# Arduino_Mopho_Connectors.net
KiCad netlist of a schematic drawn in Altium Designer
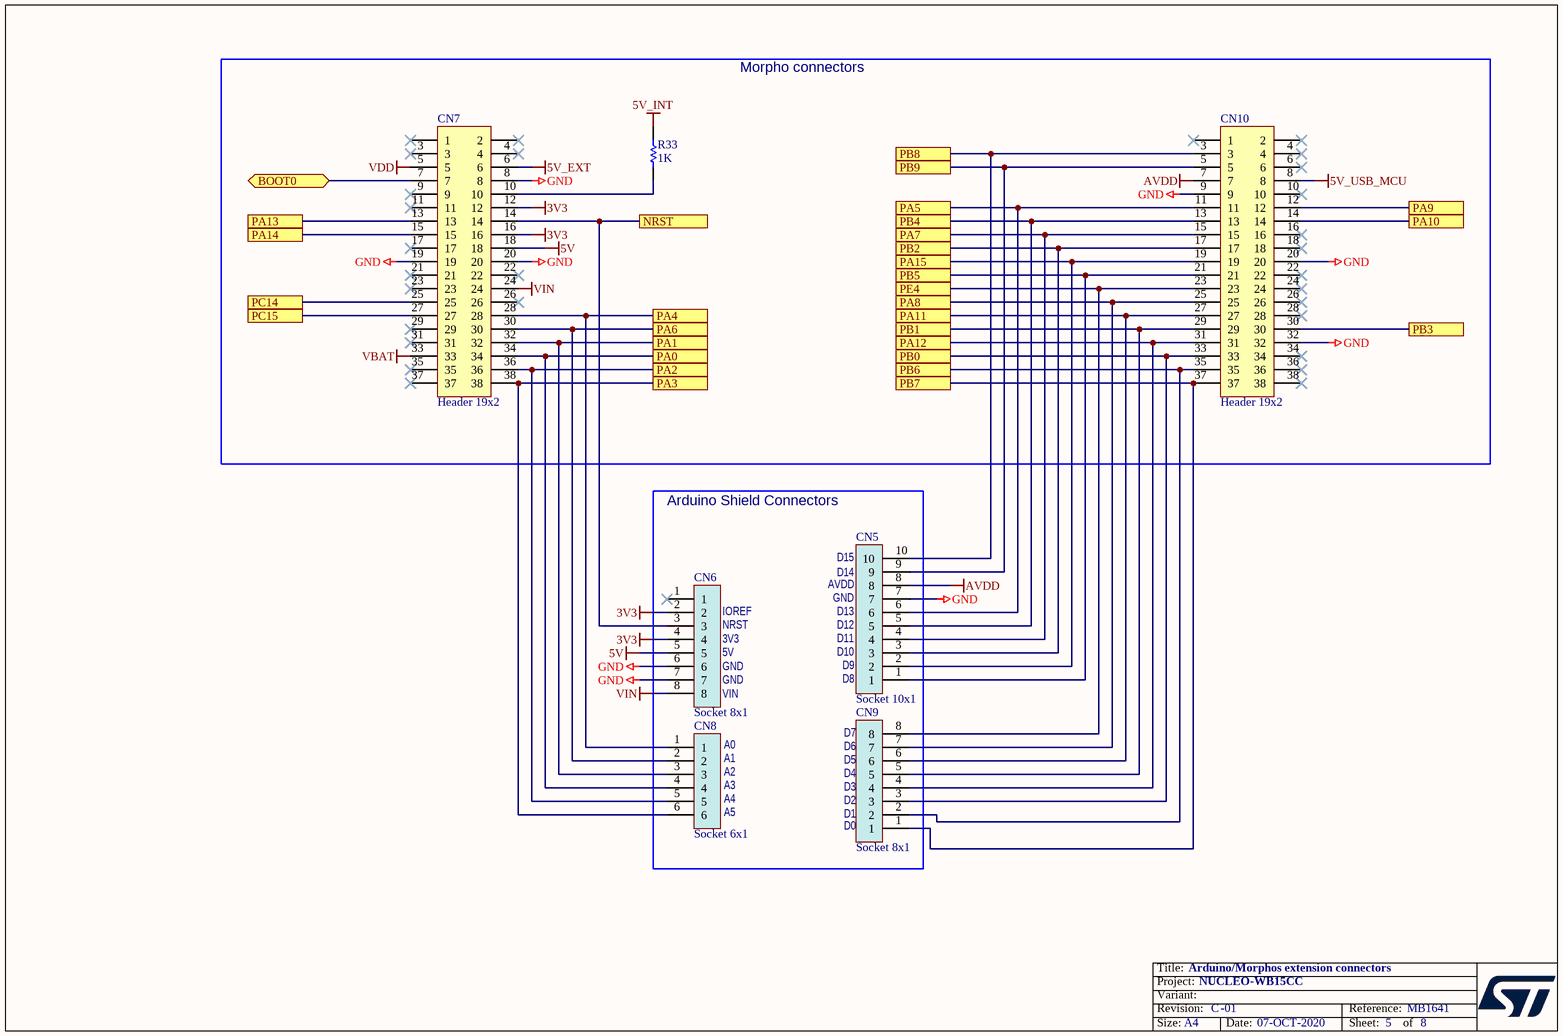
[diagram p0: Arduino_Mopho_Connectors.SchDoc]

(export (version "E")
  (design (tool "Eeschema 10.0.6"))
  (components
    (comp (ref "CN5")
      (value "Socket 10x1")
      (footprint "CON_SAMTEC_SSW-110-01-X-S")
      (description "Socket 10x1, 2.54mm, VR, TH, height 8.51/2.64mm")
      (fields
        (field (name "INTERNAL_PART_NUMBER") "MCD-02080")
        (field (name "MANUFACTURER_PART_NUMBER") "SSW-110-01-G-S")
      )
      (libsource (lib "MCD_PARTS_database") (part "Socket 10x1"))
    )
    (comp (ref "CN6")
      (value "Socket 8x1")
      (footprint "CON_SAMTEC_SSW-108-01-X-S")
      (description "Socket 8x1, 2.54mm, VR, TH, height 8.51/2.64mm")
      (fields
        (field (name "INTERNAL_PART_NUMBER") "MCD-01743")
        (field (name "MANUFACTURER_PART_NUMBER") "SSW-108-01-G-S")
      )
      (libsource (lib "MCD_PARTS_database") (part "Socket 8x1"))
    )
    (comp (ref "CN7")
      (value "Header 19x2")
      (footprint "CON_SAMTEC_TSW-119-09-X-D")
      (description "Header, 19x2, 2,54mm, VR, TH, Height 5.84mm/10.16mm")
      (fields
        (field (name "INTERNAL_PART_NUMBER") "MCD-00213")
        (field (name "MANUFACTURER_PART_NUMBER") "TSW-119-09-G-D")
      )
      (libsource (lib "MCD_PARTS_database") (part "Header 19x2"))
    )
    (comp (ref "CN8")
      (value "Socket 6x1")
      (footprint "CON_SAMTEC_SSW-106-01-X-S")
      (description "Socket 6x1, 2.54mm, VR, TH, height 8.51/2.64mm")
      (fields
        (field (name "INTERNAL_PART_NUMBER") "MCD-02079")
        (field (name "MANUFACTURER_PART_NUMBER") "SSW-106-01-G-S")
      )
      (libsource (lib "MCD_PARTS_database") (part "Socket 6x1"))
    )
    (comp (ref "CN9")
      (value "Socket 8x1")
      (footprint "CON_SAMTEC_SSW-108-01-X-S")
      (description "Socket 8x1, 2.54mm, VR, TH, height 8.51/2.64mm")
      (fields
        (field (name "INTERNAL_PART_NUMBER") "MCD-01743")
        (field (name "MANUFACTURER_PART_NUMBER") "SSW-108-01-G-S")
      )
      (libsource (lib "") (part "Socket 8x1_1"))
    )
    (comp (ref "CN10")
      (value "Header 19x2")
      (footprint "CON_SAMTEC_TSW-119-09-X-D")
      (description "Header, 19x2, 2,54mm, VR, TH, Height 5.84mm/10.16mm")
      (fields
        (field (name "INTERNAL_PART_NUMBER") "MCD-00213")
        (field (name "MANUFACTURER_PART_NUMBER") "TSW-119-09-G-D")
      )
      (libsource (lib "MCD_PARTS_database") (part "Header 19x2"))
    )
    (comp (ref "R33")
      (value "1K")
      (footprint "R0402")
      (description "Resistor,1K,0402,1%,1/16W")
      (fields
        (field (name "INTERNAL_PART_NUMBER") "MCD-00061")
        (field (name "MANUFACTURER_PART_NUMBER") "RC0402FR-071KL")
      )
      (libsource (lib "MCD_PARTS_database") (part "Resistor"))
    )
  )
  (nets
    (net (code "1") (name "/BOOT0") (class "Default")
      (node (ref "CN7") (pin "7") (pinfunction "7_7") (pintype "passive"))
    )
    (net (code "2") (name "/NRST") (class "Default")
      (node (ref "CN6") (pin "3") (pinfunction "3_3") (pintype "passive"))
      (node (ref "CN7") (pin "14") (pinfunction "14_14") (pintype "passive"))
    )
    (net (code "3") (name "/PA0") (class "Default")
      (node (ref "CN7") (pin "34") (pinfunction "34_34") (pintype "passive"))
      (node (ref "CN8") (pin "4") (pinfunction "4_4") (pintype "passive"))
    )
    (net (code "4") (name "/PA1") (class "Default")
      (node (ref "CN7") (pin "32") (pinfunction "32_32") (pintype "passive"))
      (node (ref "CN8") (pin "3") (pinfunction "3_3") (pintype "passive"))
    )
    (net (code "5") (name "/PA2") (class "Default")
      (node (ref "CN7") (pin "36") (pinfunction "36_36") (pintype "passive"))
      (node (ref "CN8") (pin "5") (pinfunction "5_5") (pintype "passive"))
    )
    (net (code "6") (name "/PA3") (class "Default")
      (node (ref "CN7") (pin "38") (pinfunction "38_38") (pintype "passive"))
      (node (ref "CN8") (pin "6") (pinfunction "6_6") (pintype "passive"))
    )
    (net (code "7") (name "/PA4") (class "Default")
      (node (ref "CN7") (pin "28") (pinfunction "28_28") (pintype "passive"))
      (node (ref "CN8") (pin "1") (pinfunction "1_1") (pintype "passive"))
    )
    (net (code "8") (name "/PA5") (class "Default")
      (node (ref "CN10") (pin "11") (pinfunction "11_11") (pintype "passive"))
      (node (ref "CN5") (pin "6") (pinfunction "6_6") (pintype "passive"))
    )
    (net (code "9") (name "/PA6") (class "Default")
      (node (ref "CN7") (pin "30") (pinfunction "30_30") (pintype "passive"))
      (node (ref "CN8") (pin "2") (pinfunction "2_2") (pintype "passive"))
    )
    (net (code "10") (name "/PA7") (class "Default")
      (node (ref "CN10") (pin "15") (pinfunction "15_15") (pintype "passive"))
      (node (ref "CN5") (pin "4") (pinfunction "4_4") (pintype "passive"))
    )
    (net (code "11") (name "/PA8") (class "Default")
      (node (ref "CN10") (pin "25") (pinfunction "25_25") (pintype "passive"))
      (node (ref "CN9") (pin "7") (pinfunction "7_7") (pintype "passive"))
    )
    (net (code "12") (name "/PA9") (class "Default")
      (node (ref "CN10") (pin "12") (pinfunction "12_12") (pintype "passive"))
    )
    (net (code "13") (name "/PA10") (class "Default")
      (node (ref "CN10") (pin "14") (pinfunction "14_14") (pintype "passive"))
    )
    (net (code "14") (name "/PA11") (class "Default")
      (node (ref "CN10") (pin "27") (pinfunction "27_27") (pintype "passive"))
      (node (ref "CN9") (pin "6") (pinfunction "6_6") (pintype "passive"))
    )
    (net (code "15") (name "/PA12") (class "Default")
      (node (ref "CN10") (pin "31") (pinfunction "31_31") (pintype "passive"))
      (node (ref "CN9") (pin "4") (pinfunction "4_4") (pintype "passive"))
    )
    (net (code "16") (name "/PA13") (class "Default")
      (node (ref "CN7") (pin "13") (pinfunction "13_13") (pintype "passive"))
    )
    (net (code "17") (name "/PA14") (class "Default")
      (node (ref "CN7") (pin "15") (pinfunction "15_15") (pintype "passive"))
    )
    (net (code "18") (name "/PA15") (class "Default")
      (node (ref "CN10") (pin "19") (pinfunction "19_19") (pintype "passive"))
      (node (ref "CN5") (pin "2") (pinfunction "2_2") (pintype "passive"))
    )
    (net (code "19") (name "/PB0") (class "Default")
      (node (ref "CN10") (pin "33") (pinfunction "33_33") (pintype "passive"))
      (node (ref "CN9") (pin "3") (pinfunction "3_3") (pintype "passive"))
    )
    (net (code "20") (name "/PB1") (class "Default")
      (node (ref "CN10") (pin "29") (pinfunction "29_29") (pintype "passive"))
      (node (ref "CN9") (pin "5") (pinfunction "5_5") (pintype "passive"))
    )
    (net (code "21") (name "/PB2") (class "Default")
      (node (ref "CN10") (pin "17") (pinfunction "17_17") (pintype "passive"))
      (node (ref "CN5") (pin "3") (pinfunction "3_3") (pintype "passive"))
    )
    (net (code "22") (name "/PB3") (class "Default")
      (node (ref "CN10") (pin "30") (pinfunction "30_30") (pintype "passive"))
    )
    (net (code "23") (name "/PB4") (class "Default")
      (node (ref "CN10") (pin "13") (pinfunction "13_13") (pintype "passive"))
      (node (ref "CN5") (pin "5") (pinfunction "5_5") (pintype "passive"))
    )
    (net (code "24") (name "/PB5") (class "Default")
      (node (ref "CN10") (pin "21") (pinfunction "21_21") (pintype "passive"))
      (node (ref "CN5") (pin "1") (pinfunction "1_1") (pintype "passive"))
    )
    (net (code "25") (name "/PB6") (class "Default")
      (node (ref "CN10") (pin "35") (pinfunction "35_35") (pintype "passive"))
      (node (ref "CN9") (pin "2") (pinfunction "2_2") (pintype "passive"))
    )
    (net (code "26") (name "/PB7") (class "Default")
      (node (ref "CN10") (pin "37") (pinfunction "37_37") (pintype "passive"))
      (node (ref "CN9") (pin "1") (pinfunction "1_1") (pintype "passive"))
    )
    (net (code "27") (name "/PB8") (class "Default")
      (node (ref "CN10") (pin "3") (pinfunction "3_3") (pintype "passive"))
      (node (ref "CN5") (pin "10") (pinfunction "10_10") (pintype "passive"))
    )
    (net (code "28") (name "/PB9") (class "Default")
      (node (ref "CN10") (pin "5") (pinfunction "5_5") (pintype "passive"))
      (node (ref "CN5") (pin "9") (pinfunction "9_9") (pintype "passive"))
    )
    (net (code "29") (name "/PC14") (class "Default")
      (node (ref "CN7") (pin "25") (pinfunction "25_25") (pintype "passive"))
    )
    (net (code "30") (name "/PC15") (class "Default")
      (node (ref "CN7") (pin "27") (pinfunction "27_27") (pintype "passive"))
    )
    (net (code "31") (name "/PE4") (class "Default")
      (node (ref "CN10") (pin "23") (pinfunction "23_23") (pintype "passive"))
      (node (ref "CN9") (pin "8") (pinfunction "8_8") (pintype "passive"))
    )
    (net (code "32") (name "3V3") (class "Default")
      (node (ref "CN6") (pin "2") (pinfunction "2_2") (pintype "passive"))
      (node (ref "CN6") (pin "4") (pinfunction "4_4") (pintype "passive"))
      (node (ref "CN7") (pin "12") (pinfunction "12_12") (pintype "passive"))
      (node (ref "CN7") (pin "16") (pinfunction "16_16") (pintype "passive"))
    )
    (net (code "33") (name "5V") (class "Default")
      (node (ref "CN6") (pin "5") (pinfunction "5_5") (pintype "passive"))
      (node (ref "CN7") (pin "18") (pinfunction "18_18") (pintype "passive"))
    )
    (net (code "34") (name "5V_EXT") (class "Default")
      (node (ref "CN7") (pin "6") (pinfunction "6_6") (pintype "passive"))
    )
    (net (code "35") (name "5V_INT") (class "Default")
      (node (ref "R33") (pin "2") (pinfunction "2_2") (pintype "passive"))
    )
    (net (code "36") (name "5V_USB_MCU") (class "Default")
      (node (ref "CN10") (pin "8") (pinfunction "8_8") (pintype "passive"))
    )
    (net (code "37") (name "AVDD") (class "Default")
      (node (ref "CN10") (pin "7") (pinfunction "7_7") (pintype "passive"))
      (node (ref "CN5") (pin "8") (pinfunction "8_8") (pintype "passive"))
    )
    (net (code "38") (name "GND") (class "Default")
      (node (ref "CN10") (pin "20") (pinfunction "20_20") (pintype "passive"))
      (node (ref "CN10") (pin "32") (pinfunction "32_32") (pintype "passive"))
      (node (ref "CN10") (pin "9") (pinfunction "9_9") (pintype "passive"))
      (node (ref "CN5") (pin "7") (pinfunction "7_7") (pintype "passive"))
      (node (ref "CN6") (pin "6") (pinfunction "6_6") (pintype "passive"))
      (node (ref "CN6") (pin "7") (pinfunction "7_7") (pintype "passive"))
      (node (ref "CN7") (pin "19") (pinfunction "19_19") (pintype "passive"))
      (node (ref "CN7") (pin "20") (pinfunction "20_20") (pintype "passive"))
      (node (ref "CN7") (pin "8") (pinfunction "8_8") (pintype "passive"))
    )
    (net (code "39") (name "Net-(CN7-Pad10)") (class "Default")
      (node (ref "CN7") (pin "10") (pinfunction "10_10") (pintype "passive"))
      (node (ref "R33") (pin "1") (pinfunction "1_1") (pintype "passive"))
    )
    (net (code "40") (name "VBAT") (class "Default")
      (node (ref "CN7") (pin "33") (pinfunction "33_33") (pintype "passive"))
    )
    (net (code "41") (name "VDD") (class "Default")
      (node (ref "CN7") (pin "5") (pinfunction "5_5") (pintype "passive"))
    )
    (net (code "42") (name "VIN") (class "Default")
      (node (ref "CN6") (pin "8") (pinfunction "8_8") (pintype "passive"))
      (node (ref "CN7") (pin "24") (pinfunction "24_24") (pintype "passive"))
    )
    (net (code "43") (name "unconnected-(CN6-Pad1)") (class "Default")
      (node (ref "CN6") (pin "1") (pinfunction "1_1") (pintype "passive+no_connect"))
    )
    (net (code "44") (name "unconnected-(CN7-Pad1)") (class "Default")
      (node (ref "CN7") (pin "1") (pinfunction "1_1") (pintype "passive+no_connect"))
    )
    (net (code "45") (name "unconnected-(CN7-Pad2)") (class "Default")
      (node (ref "CN7") (pin "2") (pinfunction "2_2") (pintype "passive+no_connect"))
    )
    (net (code "46") (name "unconnected-(CN7-Pad3)") (class "Default")
      (node (ref "CN7") (pin "3") (pinfunction "3_3") (pintype "passive+no_connect"))
    )
    (net (code "47") (name "unconnected-(CN7-Pad4)") (class "Default")
      (node (ref "CN7") (pin "4") (pinfunction "4_4") (pintype "passive+no_connect"))
    )
    (net (code "48") (name "unconnected-(CN7-Pad9)") (class "Default")
      (node (ref "CN7") (pin "9") (pinfunction "9_9") (pintype "passive+no_connect"))
    )
    (net (code "49") (name "unconnected-(CN7-Pad11)") (class "Default")
      (node (ref "CN7") (pin "11") (pinfunction "11_11") (pintype "passive+no_connect"))
    )
    (net (code "50") (name "unconnected-(CN7-Pad17)") (class "Default")
      (node (ref "CN7") (pin "17") (pinfunction "17_17") (pintype "passive+no_connect"))
    )
    (net (code "51") (name "unconnected-(CN7-Pad21)") (class "Default")
      (node (ref "CN7") (pin "21") (pinfunction "21_21") (pintype "passive+no_connect"))
    )
    (net (code "52") (name "unconnected-(CN7-Pad22)") (class "Default")
      (node (ref "CN7") (pin "22") (pinfunction "22_22") (pintype "passive+no_connect"))
    )
    (net (code "53") (name "unconnected-(CN7-Pad23)") (class "Default")
      (node (ref "CN7") (pin "23") (pinfunction "23_23") (pintype "passive+no_connect"))
    )
    (net (code "54") (name "unconnected-(CN7-Pad26)") (class "Default")
      (node (ref "CN7") (pin "26") (pinfunction "26_26") (pintype "passive+no_connect"))
    )
    (net (code "55") (name "unconnected-(CN7-Pad29)") (class "Default")
      (node (ref "CN7") (pin "29") (pinfunction "29_29") (pintype "passive+no_connect"))
    )
    (net (code "56") (name "unconnected-(CN7-Pad31)") (class "Default")
      (node (ref "CN7") (pin "31") (pinfunction "31_31") (pintype "passive+no_connect"))
    )
    (net (code "57") (name "unconnected-(CN7-Pad35)") (class "Default")
      (node (ref "CN7") (pin "35") (pinfunction "35_35") (pintype "passive+no_connect"))
    )
    (net (code "58") (name "unconnected-(CN7-Pad37)") (class "Default")
      (node (ref "CN7") (pin "37") (pinfunction "37_37") (pintype "passive+no_connect"))
    )
    (net (code "59") (name "unconnected-(CN10-Pad1)") (class "Default")
      (node (ref "CN10") (pin "1") (pinfunction "1_1") (pintype "passive+no_connect"))
    )
    (net (code "60") (name "unconnected-(CN10-Pad2)") (class "Default")
      (node (ref "CN10") (pin "2") (pinfunction "2_2") (pintype "passive+no_connect"))
    )
    (net (code "61") (name "unconnected-(CN10-Pad4)") (class "Default")
      (node (ref "CN10") (pin "4") (pinfunction "4_4") (pintype "passive+no_connect"))
    )
    (net (code "62") (name "unconnected-(CN10-Pad6)") (class "Default")
      (node (ref "CN10") (pin "6") (pinfunction "6_6") (pintype "passive+no_connect"))
    )
    (net (code "63") (name "unconnected-(CN10-Pad10)") (class "Default")
      (node (ref "CN10") (pin "10") (pinfunction "10_10") (pintype "passive+no_connect"))
    )
    (net (code "64") (name "unconnected-(CN10-Pad16)") (class "Default")
      (node (ref "CN10") (pin "16") (pinfunction "16_16") (pintype "passive+no_connect"))
    )
    (net (code "65") (name "unconnected-(CN10-Pad18)") (class "Default")
      (node (ref "CN10") (pin "18") (pinfunction "18_18") (pintype "passive+no_connect"))
    )
    (net (code "66") (name "unconnected-(CN10-Pad22)") (class "Default")
      (node (ref "CN10") (pin "22") (pinfunction "22_22") (pintype "passive+no_connect"))
    )
    (net (code "67") (name "unconnected-(CN10-Pad24)") (class "Default")
      (node (ref "CN10") (pin "24") (pinfunction "24_24") (pintype "passive+no_connect"))
    )
    (net (code "68") (name "unconnected-(CN10-Pad26)") (class "Default")
      (node (ref "CN10") (pin "26") (pinfunction "26_26") (pintype "passive+no_connect"))
    )
    (net (code "69") (name "unconnected-(CN10-Pad28)") (class "Default")
      (node (ref "CN10") (pin "28") (pinfunction "28_28") (pintype "passive+no_connect"))
    )
    (net (code "70") (name "unconnected-(CN10-Pad34)") (class "Default")
      (node (ref "CN10") (pin "34") (pinfunction "34_34") (pintype "passive+no_connect"))
    )
    (net (code "71") (name "unconnected-(CN10-Pad36)") (class "Default")
      (node (ref "CN10") (pin "36") (pinfunction "36_36") (pintype "passive+no_connect"))
    )
    (net (code "72") (name "unconnected-(CN10-Pad38)") (class "Default")
      (node (ref "CN10") (pin "38") (pinfunction "38_38") (pintype "passive+no_connect"))
    )
  )
)
